# saomr.net
KiCad netlist of a schematic drawn in EAGLE
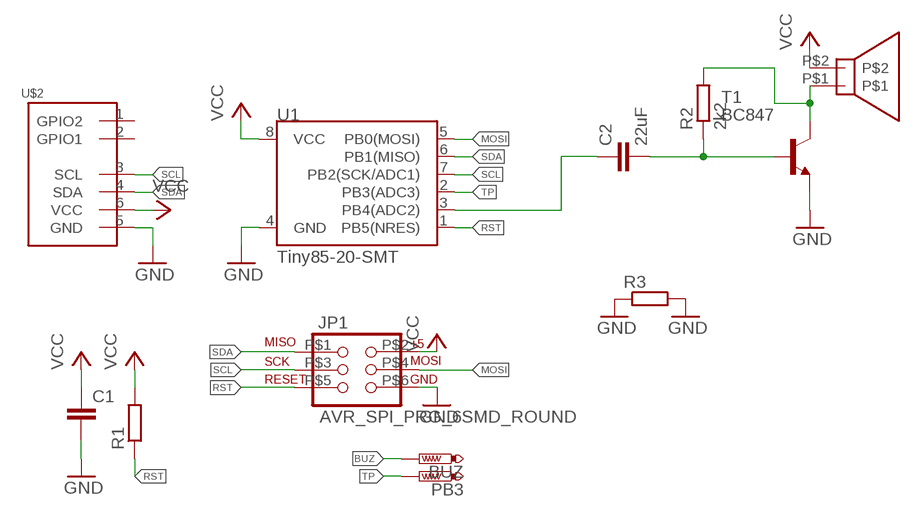
[diagram p0: schematic, sheet 1]

(export (version "E")
  (design (tool "Eeschema 10.0.6"))
  (components
    (comp (ref "BUZ")
      (value "PTR1B2,54")
      (footprint "eagle-import:B2,54")
      (libsource (lib "eagle-import") (part "PTR1B2,54"))
    )
    (comp (ref "C1")
      (value "C-EUC1206")
      (footprint "eagle-import:C1206")
      (libsource (lib "eagle-import") (part "C-EUC1206"))
    )
    (comp (ref "C2")
      (value "22uF")
      (footprint "eagle-import:C1206")
      (libsource (lib "eagle-import") (part "resistor_C-EUC1206"))
    )
    (comp (ref "JP1")
      (value "AVR_SPI_PRG_6SMD_ROUND")
      (footprint "eagle-import:2X3_SMD_PAD_ROUND")
      (libsource (lib "eagle-import") (part "AVR_SPI_PRG_6SMD_ROUND"))
    )
    (comp (ref "PB3")
      (value "PTR1B2,54")
      (footprint "eagle-import:B2,54")
      (libsource (lib "eagle-import") (part "PTR1B2,54"))
    )
    (comp (ref "R1")
      (value "R-EU_R1206")
      (footprint "eagle-import:R1206")
      (libsource (lib "eagle-import") (part "R-EU_R1206"))
    )
    (comp (ref "R2")
      (value "2k2")
      (footprint "eagle-import:R1206")
      (libsource (lib "eagle-import") (part "R-EU_R1206"))
    )
    (comp (ref "R3")
      (value "R-EU_M1206")
      (footprint "eagle-import:M1206")
      (libsource (lib "eagle-import") (part "resistor_R-EU_M1206"))
    )
    (comp (ref "T1")
      (value "BC847")
      (footprint "eagle-import:SOT23")
      (libsource (lib "eagle-import") (part "BC847"))
    )
    (comp (ref "U$1")
      (value "SPEAKERKMTG-1102")
      (footprint "eagle-import:KMTG-1102")
      (libsource (lib "eagle-import") (part "SPEAKERKMTG-1102"))
    )
    (comp (ref "U$2")
      (value "SAO-SHITTY-ADDON")
      (footprint "eagle-import:2X3_SMD")
      (libsource (lib "eagle-import") (part "SAO-SHITTY-ADDON"))
    )
    (comp (ref "U1")
      (value "Tiny85-20-SMT")
      (footprint "eagle-import:SO08-EIAJ")
      (libsource (lib "eagle-import") (part "ATTINY45TINY85-20-SMT"))
    )
  )
  (nets
    (net (code "1") (name "BUZ") (class "Default")
      (node (ref "BUZ") (pin "TP") (pinfunction "TP_TP") (pintype "input"))
      (node (ref "C2") (pin "1") (pinfunction "1_1") (pintype "passive"))
      (node (ref "U1") (pin "3") (pinfunction "PB4(ADC2)_3") (pintype "bidirectional"))
    )
    (net (code "2") (name "GND") (class "Default")
      (node (ref "C1") (pin "2") (pinfunction "2_2") (pintype "passive"))
      (node (ref "JP1") (pin "P$6") (pinfunction "6_P$6") (pintype "passive"))
      (node (ref "R3") (pin "1") (pinfunction "1_1") (pintype "passive"))
      (node (ref "R3") (pin "2") (pinfunction "2_2") (pintype "passive"))
      (node (ref "T1") (pin "2") (pinfunction "E_2") (pintype "passive"))
      (node (ref "U$2") (pin "5") (pinfunction "GND_5") (pintype "bidirectional"))
      (node (ref "U1") (pin "4") (pinfunction "GND_4") (pintype "bidirectional"))
    )
    (net (code "3") (name "MOSI") (class "Default")
      (node (ref "JP1") (pin "P$4") (pinfunction "4_P$4") (pintype "passive"))
      (node (ref "U1") (pin "5") (pinfunction "PB0(MOSI)_5") (pintype "bidirectional"))
    )
    (net (code "4") (name "Net-(T1-B)") (class "Default")
      (node (ref "C2") (pin "2") (pinfunction "2_2") (pintype "passive"))
      (node (ref "R2") (pin "1") (pinfunction "1_1") (pintype "passive"))
      (node (ref "T1") (pin "1") (pinfunction "B_1") (pintype "passive"))
    )
    (net (code "5") (name "Net-(T1-C)") (class "Default")
      (node (ref "R2") (pin "2") (pinfunction "2_2") (pintype "passive"))
      (node (ref "T1") (pin "3") (pinfunction "C_3") (pintype "passive"))
      (node (ref "U$1") (pin "P$1") (pinfunction "P$1_P$1") (pintype "bidirectional"))
    )
    (net (code "6") (name "RST") (class "Default")
      (node (ref "JP1") (pin "P$5") (pinfunction "5_P$5") (pintype "passive"))
      (node (ref "R1") (pin "1") (pinfunction "1_1") (pintype "passive"))
      (node (ref "U1") (pin "1") (pinfunction "PB5(NRES)_1") (pintype "bidirectional"))
    )
    (net (code "7") (name "SCL") (class "Default")
      (node (ref "JP1") (pin "P$3") (pinfunction "3_P$3") (pintype "passive"))
      (node (ref "U$2") (pin "3") (pinfunction "SCL_3") (pintype "bidirectional"))
      (node (ref "U1") (pin "7") (pinfunction "PB2(SCK/ADC1)_7") (pintype "bidirectional"))
    )
    (net (code "8") (name "SDA") (class "Default")
      (node (ref "JP1") (pin "P$1") (pinfunction "1_P$1") (pintype "passive"))
      (node (ref "U$2") (pin "4") (pinfunction "SDA_4") (pintype "bidirectional"))
      (node (ref "U1") (pin "6") (pinfunction "PB1(MISO)_6") (pintype "bidirectional"))
    )
    (net (code "9") (name "TP") (class "Default")
      (node (ref "PB3") (pin "TP") (pinfunction "TP_TP") (pintype "input"))
      (node (ref "U1") (pin "2") (pinfunction "PB3(ADC3)_2") (pintype "bidirectional"))
    )
    (net (code "10") (name "VCC") (class "Default")
      (node (ref "C1") (pin "1") (pinfunction "1_1") (pintype "passive"))
      (node (ref "JP1") (pin "P$2") (pinfunction "2_P$2") (pintype "passive"))
      (node (ref "R1") (pin "2") (pinfunction "2_2") (pintype "passive"))
      (node (ref "U$1") (pin "P$2") (pinfunction "P$2_P$2") (pintype "bidirectional"))
      (node (ref "U$2") (pin "6") (pinfunction "VCC_6") (pintype "bidirectional"))
      (node (ref "U1") (pin "8") (pinfunction "VCC_8") (pintype "bidirectional"))
    )
    (net (code "11") (name "unconnected-(U$2-GPIO1-Pad2)") (class "Default")
      (node (ref "U$2") (pin "2") (pinfunction "GPIO1_2") (pintype "bidirectional"))
    )
    (net (code "12") (name "unconnected-(U$2-GPIO2-Pad1)") (class "Default")
      (node (ref "U$2") (pin "1") (pinfunction "GPIO2_1") (pintype "bidirectional"))
    )
  )
)
